# other_corin.net
KiCad netlist of a schematic drawn in Altium Designer
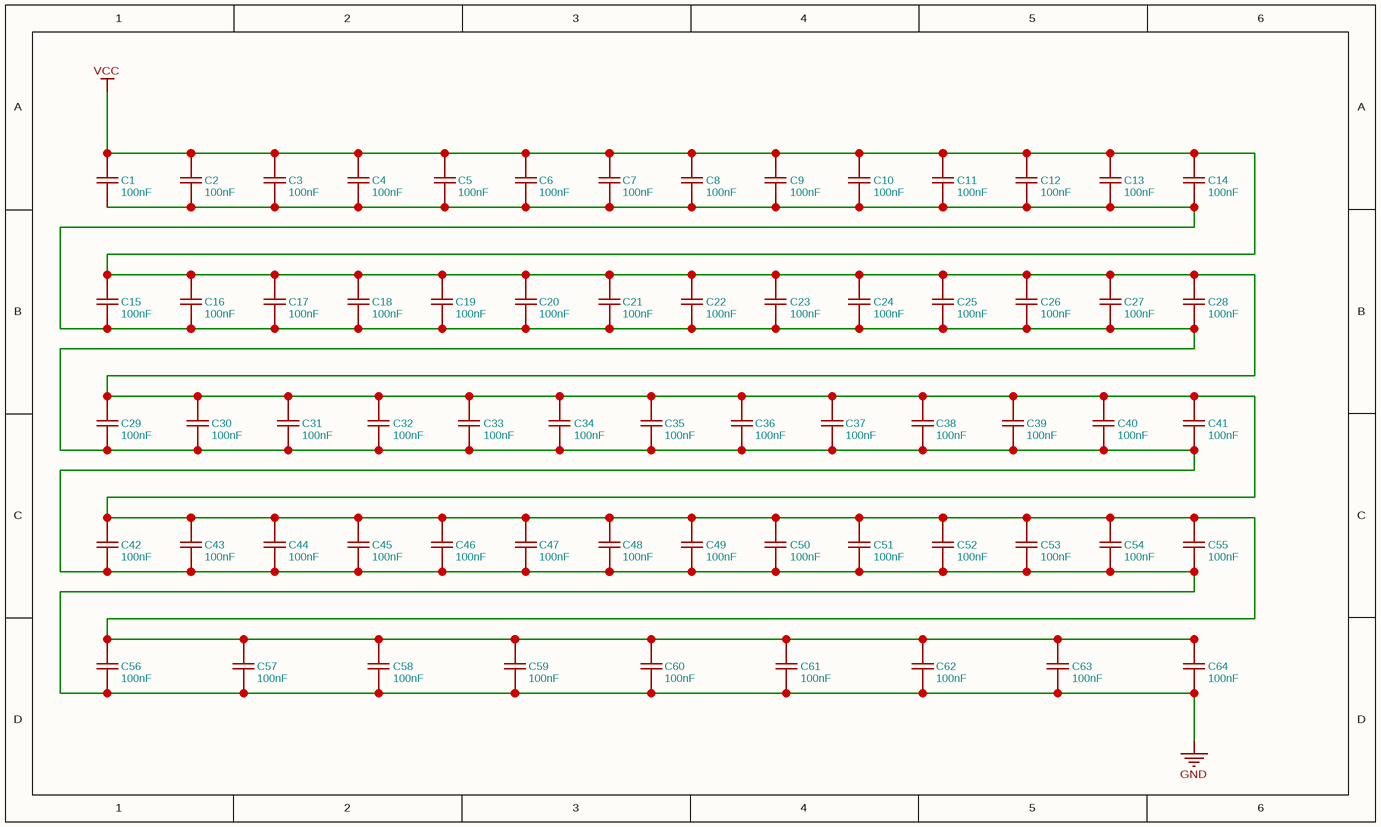
[diagram p0: other_corin.schdoc]

(export (version "E")
  (design (tool "Eeschema 10.0.6"))
  (components
    (comp (ref "C1")
      (value "100nF")
      (fields
        (field (name "BOM_MANUFACTURER PART") "CC0603KRX7R9BB104")
        (field (name "BOM_SUPPLIER PART") "C14663")
      )
      (libsource (lib "altium-import") (part "root_1_100nF_"))
    )
    (comp (ref "C2")
      (value "100nF")
      (fields
        (field (name "BOM_MANUFACTURER PART") "CC0603KRX7R9BB104")
        (field (name "BOM_SUPPLIER PART") "C14663")
      )
      (libsource (lib "altium-import") (part "root_1_100nF_"))
    )
    (comp (ref "C3")
      (value "100nF")
      (fields
        (field (name "BOM_MANUFACTURER PART") "CC0603KRX7R9BB104")
        (field (name "BOM_SUPPLIER PART") "C14663")
      )
      (libsource (lib "altium-import") (part "root_1_100nF_"))
    )
    (comp (ref "C4")
      (value "100nF")
      (fields
        (field (name "BOM_MANUFACTURER PART") "CC0603KRX7R9BB104")
        (field (name "BOM_SUPPLIER PART") "C14663")
      )
      (libsource (lib "altium-import") (part "root_1_100nF_"))
    )
    (comp (ref "C5")
      (value "100nF")
      (fields
        (field (name "BOM_MANUFACTURER PART") "CC0603KRX7R9BB104")
        (field (name "BOM_SUPPLIER PART") "C14663")
      )
      (libsource (lib "altium-import") (part "root_1_100nF_"))
    )
    (comp (ref "C6")
      (value "100nF")
      (fields
        (field (name "BOM_MANUFACTURER PART") "CC0603KRX7R9BB104")
        (field (name "BOM_SUPPLIER PART") "C14663")
      )
      (libsource (lib "altium-import") (part "root_1_100nF_"))
    )
    (comp (ref "C7")
      (value "100nF")
      (fields
        (field (name "BOM_MANUFACTURER PART") "CC0603KRX7R9BB104")
        (field (name "BOM_SUPPLIER PART") "C14663")
      )
      (libsource (lib "altium-import") (part "root_1_100nF_"))
    )
    (comp (ref "C8")
      (value "100nF")
      (fields
        (field (name "BOM_MANUFACTURER PART") "CC0603KRX7R9BB104")
        (field (name "BOM_SUPPLIER PART") "C14663")
      )
      (libsource (lib "altium-import") (part "root_1_100nF_"))
    )
    (comp (ref "C9")
      (value "100nF")
      (fields
        (field (name "BOM_MANUFACTURER PART") "CC0603KRX7R9BB104")
        (field (name "BOM_SUPPLIER PART") "C14663")
      )
      (libsource (lib "altium-import") (part "root_1_100nF_"))
    )
    (comp (ref "C10")
      (value "100nF")
      (fields
        (field (name "BOM_MANUFACTURER PART") "CC0603KRX7R9BB104")
        (field (name "BOM_SUPPLIER PART") "C14663")
      )
      (libsource (lib "altium-import") (part "root_1_100nF_"))
    )
    (comp (ref "C11")
      (value "100nF")
      (fields
        (field (name "BOM_MANUFACTURER PART") "CC0603KRX7R9BB104")
        (field (name "BOM_SUPPLIER PART") "C14663")
      )
      (libsource (lib "altium-import") (part "root_1_100nF_"))
    )
    (comp (ref "C12")
      (value "100nF")
      (fields
        (field (name "BOM_MANUFACTURER PART") "CC0603KRX7R9BB104")
        (field (name "BOM_SUPPLIER PART") "C14663")
      )
      (libsource (lib "altium-import") (part "root_1_100nF_"))
    )
    (comp (ref "C13")
      (value "100nF")
      (fields
        (field (name "BOM_MANUFACTURER PART") "CC0603KRX7R9BB104")
        (field (name "BOM_SUPPLIER PART") "C14663")
      )
      (libsource (lib "altium-import") (part "root_1_100nF_"))
    )
    (comp (ref "C14")
      (value "100nF")
      (fields
        (field (name "BOM_MANUFACTURER PART") "CC0603KRX7R9BB104")
        (field (name "BOM_SUPPLIER PART") "C14663")
      )
      (libsource (lib "altium-import") (part "root_1_100nF_"))
    )
    (comp (ref "C15")
      (value "100nF")
      (fields
        (field (name "BOM_MANUFACTURER PART") "CC0603KRX7R9BB104")
        (field (name "BOM_SUPPLIER PART") "C14663")
      )
      (libsource (lib "altium-import") (part "root_1_100nF_"))
    )
    (comp (ref "C16")
      (value "100nF")
      (fields
        (field (name "BOM_MANUFACTURER PART") "CC0603KRX7R9BB104")
        (field (name "BOM_SUPPLIER PART") "C14663")
      )
      (libsource (lib "altium-import") (part "root_1_100nF_"))
    )
    (comp (ref "C17")
      (value "100nF")
      (fields
        (field (name "BOM_MANUFACTURER PART") "CC0603KRX7R9BB104")
        (field (name "BOM_SUPPLIER PART") "C14663")
      )
      (libsource (lib "altium-import") (part "root_1_100nF_"))
    )
    (comp (ref "C18")
      (value "100nF")
      (fields
        (field (name "BOM_MANUFACTURER PART") "CC0603KRX7R9BB104")
        (field (name "BOM_SUPPLIER PART") "C14663")
      )
      (libsource (lib "altium-import") (part "root_1_100nF_"))
    )
    (comp (ref "C19")
      (value "100nF")
      (fields
        (field (name "BOM_MANUFACTURER PART") "CC0603KRX7R9BB104")
        (field (name "BOM_SUPPLIER PART") "C14663")
      )
      (libsource (lib "altium-import") (part "root_1_100nF_"))
    )
    (comp (ref "C20")
      (value "100nF")
      (fields
        (field (name "BOM_MANUFACTURER PART") "CC0603KRX7R9BB104")
        (field (name "BOM_SUPPLIER PART") "C14663")
      )
      (libsource (lib "altium-import") (part "root_1_100nF_"))
    )
    (comp (ref "C21")
      (value "100nF")
      (fields
        (field (name "BOM_MANUFACTURER PART") "CC0603KRX7R9BB104")
        (field (name "BOM_SUPPLIER PART") "C14663")
      )
      (libsource (lib "altium-import") (part "root_1_100nF_"))
    )
    (comp (ref "C22")
      (value "100nF")
      (fields
        (field (name "BOM_MANUFACTURER PART") "CC0603KRX7R9BB104")
        (field (name "BOM_SUPPLIER PART") "C14663")
      )
      (libsource (lib "altium-import") (part "root_1_100nF_"))
    )
    (comp (ref "C23")
      (value "100nF")
      (fields
        (field (name "BOM_MANUFACTURER PART") "CC0603KRX7R9BB104")
        (field (name "BOM_SUPPLIER PART") "C14663")
      )
      (libsource (lib "altium-import") (part "root_1_100nF_"))
    )
    (comp (ref "C24")
      (value "100nF")
      (fields
        (field (name "BOM_MANUFACTURER PART") "CC0603KRX7R9BB104")
        (field (name "BOM_SUPPLIER PART") "C14663")
      )
      (libsource (lib "altium-import") (part "root_1_100nF_"))
    )
    (comp (ref "C25")
      (value "100nF")
      (fields
        (field (name "BOM_MANUFACTURER PART") "CC0603KRX7R9BB104")
        (field (name "BOM_SUPPLIER PART") "C14663")
      )
      (libsource (lib "altium-import") (part "root_1_100nF_"))
    )
    (comp (ref "C26")
      (value "100nF")
      (fields
        (field (name "BOM_MANUFACTURER PART") "CC0603KRX7R9BB104")
        (field (name "BOM_SUPPLIER PART") "C14663")
      )
      (libsource (lib "altium-import") (part "root_1_100nF_"))
    )
    (comp (ref "C27")
      (value "100nF")
      (fields
        (field (name "BOM_MANUFACTURER PART") "CC0603KRX7R9BB104")
        (field (name "BOM_SUPPLIER PART") "C14663")
      )
      (libsource (lib "altium-import") (part "root_1_100nF_"))
    )
    (comp (ref "C28")
      (value "100nF")
      (fields
        (field (name "BOM_MANUFACTURER PART") "CC0603KRX7R9BB104")
        (field (name "BOM_SUPPLIER PART") "C14663")
      )
      (libsource (lib "altium-import") (part "root_1_100nF_"))
    )
    (comp (ref "C29")
      (value "100nF")
      (fields
        (field (name "BOM_MANUFACTURER PART") "CC0603KRX7R9BB104")
        (field (name "BOM_SUPPLIER PART") "C14663")
      )
      (libsource (lib "altium-import") (part "root_1_100nF_"))
    )
    (comp (ref "C30")
      (value "100nF")
      (fields
        (field (name "BOM_MANUFACTURER PART") "CC0603KRX7R9BB104")
        (field (name "BOM_SUPPLIER PART") "C14663")
      )
      (libsource (lib "altium-import") (part "root_1_100nF_"))
    )
    (comp (ref "C31")
      (value "100nF")
      (fields
        (field (name "BOM_MANUFACTURER PART") "CC0603KRX7R9BB104")
        (field (name "BOM_SUPPLIER PART") "C14663")
      )
      (libsource (lib "altium-import") (part "root_1_100nF_"))
    )
    (comp (ref "C32")
      (value "100nF")
      (fields
        (field (name "BOM_MANUFACTURER PART") "CC0603KRX7R9BB104")
        (field (name "BOM_SUPPLIER PART") "C14663")
      )
      (libsource (lib "altium-import") (part "root_1_100nF_"))
    )
    (comp (ref "C33")
      (value "100nF")
      (fields
        (field (name "BOM_MANUFACTURER PART") "CC0603KRX7R9BB104")
        (field (name "BOM_SUPPLIER PART") "C14663")
      )
      (libsource (lib "altium-import") (part "root_1_100nF_"))
    )
    (comp (ref "C34")
      (value "100nF")
      (fields
        (field (name "BOM_MANUFACTURER PART") "CC0603KRX7R9BB104")
        (field (name "BOM_SUPPLIER PART") "C14663")
      )
      (libsource (lib "altium-import") (part "root_1_100nF_"))
    )
    (comp (ref "C35")
      (value "100nF")
      (fields
        (field (name "BOM_MANUFACTURER PART") "CC0603KRX7R9BB104")
        (field (name "BOM_SUPPLIER PART") "C14663")
      )
      (libsource (lib "altium-import") (part "root_1_100nF_"))
    )
    (comp (ref "C36")
      (value "100nF")
      (fields
        (field (name "BOM_MANUFACTURER PART") "CC0603KRX7R9BB104")
        (field (name "BOM_SUPPLIER PART") "C14663")
      )
      (libsource (lib "altium-import") (part "root_1_100nF_"))
    )
    (comp (ref "C37")
      (value "100nF")
      (fields
        (field (name "BOM_MANUFACTURER PART") "CC0603KRX7R9BB104")
        (field (name "BOM_SUPPLIER PART") "C14663")
      )
      (libsource (lib "altium-import") (part "root_1_100nF_"))
    )
    (comp (ref "C38")
      (value "100nF")
      (fields
        (field (name "BOM_MANUFACTURER PART") "CC0603KRX7R9BB104")
        (field (name "BOM_SUPPLIER PART") "C14663")
      )
      (libsource (lib "altium-import") (part "root_1_100nF_"))
    )
    (comp (ref "C39")
      (value "100nF")
      (fields
        (field (name "BOM_MANUFACTURER PART") "CC0603KRX7R9BB104")
        (field (name "BOM_SUPPLIER PART") "C14663")
      )
      (libsource (lib "altium-import") (part "root_1_100nF_"))
    )
    (comp (ref "C40")
      (value "100nF")
      (fields
        (field (name "BOM_MANUFACTURER PART") "CC0603KRX7R9BB104")
        (field (name "BOM_SUPPLIER PART") "C14663")
      )
      (libsource (lib "altium-import") (part "root_1_100nF_"))
    )
    (comp (ref "C41")
      (value "100nF")
      (fields
        (field (name "BOM_MANUFACTURER PART") "CC0603KRX7R9BB104")
        (field (name "BOM_SUPPLIER PART") "C14663")
      )
      (libsource (lib "altium-import") (part "root_1_100nF_"))
    )
    (comp (ref "C42")
      (value "100nF")
      (fields
        (field (name "BOM_MANUFACTURER PART") "CC0603KRX7R9BB104")
        (field (name "BOM_SUPPLIER PART") "C14663")
      )
      (libsource (lib "altium-import") (part "root_1_100nF_"))
    )
    (comp (ref "C43")
      (value "100nF")
      (fields
        (field (name "BOM_MANUFACTURER PART") "CC0603KRX7R9BB104")
        (field (name "BOM_SUPPLIER PART") "C14663")
      )
      (libsource (lib "altium-import") (part "root_1_100nF_"))
    )
    (comp (ref "C44")
      (value "100nF")
      (fields
        (field (name "BOM_MANUFACTURER PART") "CC0603KRX7R9BB104")
        (field (name "BOM_SUPPLIER PART") "C14663")
      )
      (libsource (lib "altium-import") (part "root_1_100nF_"))
    )
    (comp (ref "C45")
      (value "100nF")
      (fields
        (field (name "BOM_MANUFACTURER PART") "CC0603KRX7R9BB104")
        (field (name "BOM_SUPPLIER PART") "C14663")
      )
      (libsource (lib "altium-import") (part "root_1_100nF_"))
    )
    (comp (ref "C46")
      (value "100nF")
      (fields
        (field (name "BOM_MANUFACTURER PART") "CC0603KRX7R9BB104")
        (field (name "BOM_SUPPLIER PART") "C14663")
      )
      (libsource (lib "altium-import") (part "root_1_100nF_"))
    )
    (comp (ref "C47")
      (value "100nF")
      (fields
        (field (name "BOM_MANUFACTURER PART") "CC0603KRX7R9BB104")
        (field (name "BOM_SUPPLIER PART") "C14663")
      )
      (libsource (lib "altium-import") (part "root_1_100nF_"))
    )
    (comp (ref "C48")
      (value "100nF")
      (fields
        (field (name "BOM_MANUFACTURER PART") "CC0603KRX7R9BB104")
        (field (name "BOM_SUPPLIER PART") "C14663")
      )
      (libsource (lib "altium-import") (part "root_1_100nF_"))
    )
    (comp (ref "C49")
      (value "100nF")
      (fields
        (field (name "BOM_MANUFACTURER PART") "CC0603KRX7R9BB104")
        (field (name "BOM_SUPPLIER PART") "C14663")
      )
      (libsource (lib "altium-import") (part "root_1_100nF_"))
    )
    (comp (ref "C50")
      (value "100nF")
      (fields
        (field (name "BOM_MANUFACTURER PART") "CC0603KRX7R9BB104")
        (field (name "BOM_SUPPLIER PART") "C14663")
      )
      (libsource (lib "altium-import") (part "root_1_100nF_"))
    )
    (comp (ref "C51")
      (value "100nF")
      (fields
        (field (name "BOM_MANUFACTURER PART") "CC0603KRX7R9BB104")
        (field (name "BOM_SUPPLIER PART") "C14663")
      )
      (libsource (lib "altium-import") (part "root_1_100nF_"))
    )
    (comp (ref "C52")
      (value "100nF")
      (fields
        (field (name "BOM_MANUFACTURER PART") "CC0603KRX7R9BB104")
        (field (name "BOM_SUPPLIER PART") "C14663")
      )
      (libsource (lib "altium-import") (part "root_1_100nF_"))
    )
    (comp (ref "C53")
      (value "100nF")
      (fields
        (field (name "BOM_MANUFACTURER PART") "CC0603KRX7R9BB104")
        (field (name "BOM_SUPPLIER PART") "C14663")
      )
      (libsource (lib "altium-import") (part "root_1_100nF_"))
    )
    (comp (ref "C54")
      (value "100nF")
      (fields
        (field (name "BOM_MANUFACTURER PART") "CC0603KRX7R9BB104")
        (field (name "BOM_SUPPLIER PART") "C14663")
      )
      (libsource (lib "altium-import") (part "root_1_100nF_"))
    )
    (comp (ref "C55")
      (value "100nF")
      (fields
        (field (name "BOM_MANUFACTURER PART") "CC0603KRX7R9BB104")
        (field (name "BOM_SUPPLIER PART") "C14663")
      )
      (libsource (lib "altium-import") (part "root_1_100nF_"))
    )
    (comp (ref "C56")
      (value "100nF")
      (fields
        (field (name "BOM_MANUFACTURER PART") "CC0603KRX7R9BB104")
        (field (name "BOM_SUPPLIER PART") "C14663")
      )
      (libsource (lib "altium-import") (part "root_1_100nF_"))
    )
    (comp (ref "C57")
      (value "100nF")
      (fields
        (field (name "BOM_MANUFACTURER PART") "CC0603KRX7R9BB104")
        (field (name "BOM_SUPPLIER PART") "C14663")
      )
      (libsource (lib "altium-import") (part "root_1_100nF_"))
    )
    (comp (ref "C58")
      (value "100nF")
      (fields
        (field (name "BOM_MANUFACTURER PART") "CC0603KRX7R9BB104")
        (field (name "BOM_SUPPLIER PART") "C14663")
      )
      (libsource (lib "altium-import") (part "root_1_100nF_"))
    )
    (comp (ref "C59")
      (value "100nF")
      (fields
        (field (name "BOM_MANUFACTURER PART") "CC0603KRX7R9BB104")
        (field (name "BOM_SUPPLIER PART") "C14663")
      )
      (libsource (lib "altium-import") (part "root_1_100nF_"))
    )
    (comp (ref "C60")
      (value "100nF")
      (fields
        (field (name "BOM_MANUFACTURER PART") "CC0603KRX7R9BB104")
        (field (name "BOM_SUPPLIER PART") "C14663")
      )
      (libsource (lib "altium-import") (part "root_1_100nF_"))
    )
    (comp (ref "C61")
      (value "100nF")
      (fields
        (field (name "BOM_MANUFACTURER PART") "CC0603KRX7R9BB104")
        (field (name "BOM_SUPPLIER PART") "C14663")
      )
      (libsource (lib "altium-import") (part "root_1_100nF_"))
    )
    (comp (ref "C62")
      (value "100nF")
      (fields
        (field (name "BOM_MANUFACTURER PART") "CC0603KRX7R9BB104")
        (field (name "BOM_SUPPLIER PART") "C14663")
      )
      (libsource (lib "altium-import") (part "root_1_100nF_"))
    )
    (comp (ref "C63")
      (value "100nF")
      (fields
        (field (name "BOM_MANUFACTURER PART") "CC0603KRX7R9BB104")
        (field (name "BOM_SUPPLIER PART") "C14663")
      )
      (libsource (lib "altium-import") (part "root_1_100nF_"))
    )
    (comp (ref "C64")
      (value "100nF")
      (fields
        (field (name "BOM_MANUFACTURER PART") "CC0603KRX7R9BB104")
        (field (name "BOM_SUPPLIER PART") "C14663")
      )
      (libsource (lib "altium-import") (part "root_1_100nF_"))
    )
  )
  (nets
    (net (code "1") (name "GND") (class "Default")
      (node (ref "C1") (pin "1") (pinfunction "1_1") (pintype "passive"))
      (node (ref "C10") (pin "1") (pinfunction "1_1") (pintype "passive"))
      (node (ref "C11") (pin "1") (pinfunction "1_1") (pintype "passive"))
      (node (ref "C12") (pin "1") (pinfunction "1_1") (pintype "passive"))
      (node (ref "C13") (pin "1") (pinfunction "1_1") (pintype "passive"))
      (node (ref "C14") (pin "1") (pinfunction "1_1") (pintype "passive"))
      (node (ref "C15") (pin "1") (pinfunction "1_1") (pintype "passive"))
      (node (ref "C16") (pin "1") (pinfunction "1_1") (pintype "passive"))
      (node (ref "C17") (pin "1") (pinfunction "1_1") (pintype "passive"))
      (node (ref "C18") (pin "1") (pinfunction "1_1") (pintype "passive"))
      (node (ref "C19") (pin "1") (pinfunction "1_1") (pintype "passive"))
      (node (ref "C2") (pin "1") (pinfunction "1_1") (pintype "passive"))
      (node (ref "C20") (pin "1") (pinfunction "1_1") (pintype "passive"))
      (node (ref "C21") (pin "1") (pinfunction "1_1") (pintype "passive"))
      (node (ref "C22") (pin "1") (pinfunction "1_1") (pintype "passive"))
      (node (ref "C23") (pin "1") (pinfunction "1_1") (pintype "passive"))
      (node (ref "C24") (pin "1") (pinfunction "1_1") (pintype "passive"))
      (node (ref "C25") (pin "1") (pinfunction "1_1") (pintype "passive"))
      (node (ref "C26") (pin "1") (pinfunction "1_1") (pintype "passive"))
      (node (ref "C27") (pin "1") (pinfunction "1_1") (pintype "passive"))
      (node (ref "C28") (pin "1") (pinfunction "1_1") (pintype "passive"))
      (node (ref "C29") (pin "1") (pinfunction "1_1") (pintype "passive"))
      (node (ref "C3") (pin "1") (pinfunction "1_1") (pintype "passive"))
      (node (ref "C30") (pin "1") (pinfunction "1_1") (pintype "passive"))
      (node (ref "C31") (pin "1") (pinfunction "1_1") (pintype "passive"))
      (node (ref "C32") (pin "1") (pinfunction "1_1") (pintype "passive"))
      (node (ref "C33") (pin "1") (pinfunction "1_1") (pintype "passive"))
      (node (ref "C34") (pin "1") (pinfunction "1_1") (pintype "passive"))
      (node (ref "C35") (pin "1") (pinfunction "1_1") (pintype "passive"))
      (node (ref "C36") (pin "1") (pinfunction "1_1") (pintype "passive"))
      (node (ref "C37") (pin "1") (pinfunction "1_1") (pintype "passive"))
      (node (ref "C38") (pin "1") (pinfunction "1_1") (pintype "passive"))
      (node (ref "C39") (pin "1") (pinfunction "1_1") (pintype "passive"))
      (node (ref "C4") (pin "1") (pinfunction "1_1") (pintype "passive"))
      (node (ref "C40") (pin "1") (pinfunction "1_1") (pintype "passive"))
      (node (ref "C41") (pin "1") (pinfunction "1_1") (pintype "passive"))
      (node (ref "C42") (pin "1") (pinfunction "1_1") (pintype "passive"))
      (node (ref "C43") (pin "1") (pinfunction "1_1") (pintype "passive"))
      (node (ref "C44") (pin "1") (pinfunction "1_1") (pintype "passive"))
      (node (ref "C45") (pin "1") (pinfunction "1_1") (pintype "passive"))
      (node (ref "C46") (pin "1") (pinfunction "1_1") (pintype "passive"))
      (node (ref "C47") (pin "1") (pinfunction "1_1") (pintype "passive"))
      (node (ref "C48") (pin "1") (pinfunction "1_1") (pintype "passive"))
      (node (ref "C49") (pin "1") (pinfunction "1_1") (pintype "passive"))
      (node (ref "C5") (pin "1") (pinfunction "1_1") (pintype "passive"))
      (node (ref "C50") (pin "1") (pinfunction "1_1") (pintype "passive"))
      (node (ref "C51") (pin "1") (pinfunction "1_1") (pintype "passive"))
      (node (ref "C52") (pin "1") (pinfunction "1_1") (pintype "passive"))
      (node (ref "C53") (pin "1") (pinfunction "1_1") (pintype "passive"))
      (node (ref "C54") (pin "1") (pinfunction "1_1") (pintype "passive"))
      (node (ref "C55") (pin "1") (pinfunction "1_1") (pintype "passive"))
      (node (ref "C56") (pin "1") (pinfunction "1_1") (pintype "passive"))
      (node (ref "C57") (pin "1") (pinfunction "1_1") (pintype "passive"))
      (node (ref "C58") (pin "1") (pinfunction "1_1") (pintype "passive"))
      (node (ref "C59") (pin "1") (pinfunction "1_1") (pintype "passive"))
      (node (ref "C6") (pin "1") (pinfunction "1_1") (pintype "passive"))
      (node (ref "C60") (pin "1") (pinfunction "1_1") (pintype "passive"))
      (node (ref "C61") (pin "1") (pinfunction "1_1") (pintype "passive"))
      (node (ref "C62") (pin "1") (pinfunction "1_1") (pintype "passive"))
      (node (ref "C63") (pin "1") (pinfunction "1_1") (pintype "passive"))
      (node (ref "C64") (pin "1") (pinfunction "1_1") (pintype "passive"))
      (node (ref "C7") (pin "1") (pinfunction "1_1") (pintype "passive"))
      (node (ref "C8") (pin "1") (pinfunction "1_1") (pintype "passive"))
      (node (ref "C9") (pin "1") (pinfunction "1_1") (pintype "passive"))
    )
    (net (code "2") (name "VCC") (class "Default")
      (node (ref "C1") (pin "2") (pinfunction "2_2") (pintype "passive"))
      (node (ref "C10") (pin "2") (pinfunction "2_2") (pintype "passive"))
      (node (ref "C11") (pin "2") (pinfunction "2_2") (pintype "passive"))
      (node (ref "C12") (pin "2") (pinfunction "2_2") (pintype "passive"))
      (node (ref "C13") (pin "2") (pinfunction "2_2") (pintype "passive"))
      (node (ref "C14") (pin "2") (pinfunction "2_2") (pintype "passive"))
      (node (ref "C15") (pin "2") (pinfunction "2_2") (pintype "passive"))
      (node (ref "C16") (pin "2") (pinfunction "2_2") (pintype "passive"))
      (node (ref "C17") (pin "2") (pinfunction "2_2") (pintype "passive"))
      (node (ref "C18") (pin "2") (pinfunction "2_2") (pintype "passive"))
      (node (ref "C19") (pin "2") (pinfunction "2_2") (pintype "passive"))
      (node (ref "C2") (pin "2") (pinfunction "2_2") (pintype "passive"))
      (node (ref "C20") (pin "2") (pinfunction "2_2") (pintype "passive"))
      (node (ref "C21") (pin "2") (pinfunction "2_2") (pintype "passive"))
      (node (ref "C22") (pin "2") (pinfunction "2_2") (pintype "passive"))
      (node (ref "C23") (pin "2") (pinfunction "2_2") (pintype "passive"))
      (node (ref "C24") (pin "2") (pinfunction "2_2") (pintype "passive"))
      (node (ref "C25") (pin "2") (pinfunction "2_2") (pintype "passive"))
      (node (ref "C26") (pin "2") (pinfunction "2_2") (pintype "passive"))
      (node (ref "C27") (pin "2") (pinfunction "2_2") (pintype "passive"))
      (node (ref "C28") (pin "2") (pinfunction "2_2") (pintype "passive"))
      (node (ref "C29") (pin "2") (pinfunction "2_2") (pintype "passive"))
      (node (ref "C3") (pin "2") (pinfunction "2_2") (pintype "passive"))
      (node (ref "C30") (pin "2") (pinfunction "2_2") (pintype "passive"))
      (node (ref "C31") (pin "2") (pinfunction "2_2") (pintype "passive"))
      (node (ref "C32") (pin "2") (pinfunction "2_2") (pintype "passive"))
      (node (ref "C33") (pin "2") (pinfunction "2_2") (pintype "passive"))
      (node (ref "C34") (pin "2") (pinfunction "2_2") (pintype "passive"))
      (node (ref "C35") (pin "2") (pinfunction "2_2") (pintype "passive"))
      (node (ref "C36") (pin "2") (pinfunction "2_2") (pintype "passive"))
      (node (ref "C37") (pin "2") (pinfunction "2_2") (pintype "passive"))
      (node (ref "C38") (pin "2") (pinfunction "2_2") (pintype "passive"))
      (node (ref "C39") (pin "2") (pinfunction "2_2") (pintype "passive"))
      (node (ref "C4") (pin "2") (pinfunction "2_2") (pintype "passive"))
      (node (ref "C40") (pin "2") (pinfunction "2_2") (pintype "passive"))
      (node (ref "C41") (pin "2") (pinfunction "2_2") (pintype "passive"))
      (node (ref "C42") (pin "2") (pinfunction "2_2") (pintype "passive"))
      (node (ref "C43") (pin "2") (pinfunction "2_2") (pintype "passive"))
      (node (ref "C44") (pin "2") (pinfunction "2_2") (pintype "passive"))
      (node (ref "C45") (pin "2") (pinfunction "2_2") (pintype "passive"))
      (node (ref "C46") (pin "2") (pinfunction "2_2") (pintype "passive"))
      (node (ref "C47") (pin "2") (pinfunction "2_2") (pintype "passive"))
      (node (ref "C48") (pin "2") (pinfunction "2_2") (pintype "passive"))
      (node (ref "C49") (pin "2") (pinfunction "2_2") (pintype "passive"))
      (node (ref "C5") (pin "2") (pinfunction "2_2") (pintype "passive"))
      (node (ref "C50") (pin "2") (pinfunction "2_2") (pintype "passive"))
      (node (ref "C51") (pin "2") (pinfunction "2_2") (pintype "passive"))
      (node (ref "C52") (pin "2") (pinfunction "2_2") (pintype "passive"))
      (node (ref "C53") (pin "2") (pinfunction "2_2") (pintype "passive"))
      (node (ref "C54") (pin "2") (pinfunction "2_2") (pintype "passive"))
      (node (ref "C55") (pin "2") (pinfunction "2_2") (pintype "passive"))
      (node (ref "C56") (pin "2") (pinfunction "2_2") (pintype "passive"))
      (node (ref "C57") (pin "2") (pinfunction "2_2") (pintype "passive"))
      (node (ref "C58") (pin "2") (pinfunction "2_2") (pintype "passive"))
      (node (ref "C59") (pin "2") (pinfunction "2_2") (pintype "passive"))
      (node (ref "C6") (pin "2") (pinfunction "2_2") (pintype "passive"))
      (node (ref "C60") (pin "2") (pinfunction "2_2") (pintype "passive"))
      (node (ref "C61") (pin "2") (pinfunction "2_2") (pintype "passive"))
      (node (ref "C62") (pin "2") (pinfunction "2_2") (pintype "passive"))
      (node (ref "C63") (pin "2") (pinfunction "2_2") (pintype "passive"))
      (node (ref "C64") (pin "2") (pinfunction "2_2") (pintype "passive"))
      (node (ref "C7") (pin "2") (pinfunction "2_2") (pintype "passive"))
      (node (ref "C8") (pin "2") (pinfunction "2_2") (pintype "passive"))
      (node (ref "C9") (pin "2") (pinfunction "2_2") (pintype "passive"))
    )
  )
)
